# SCH_BlackRacer_team.net
KiCad netlist of a schematic drawn in EasyEDA
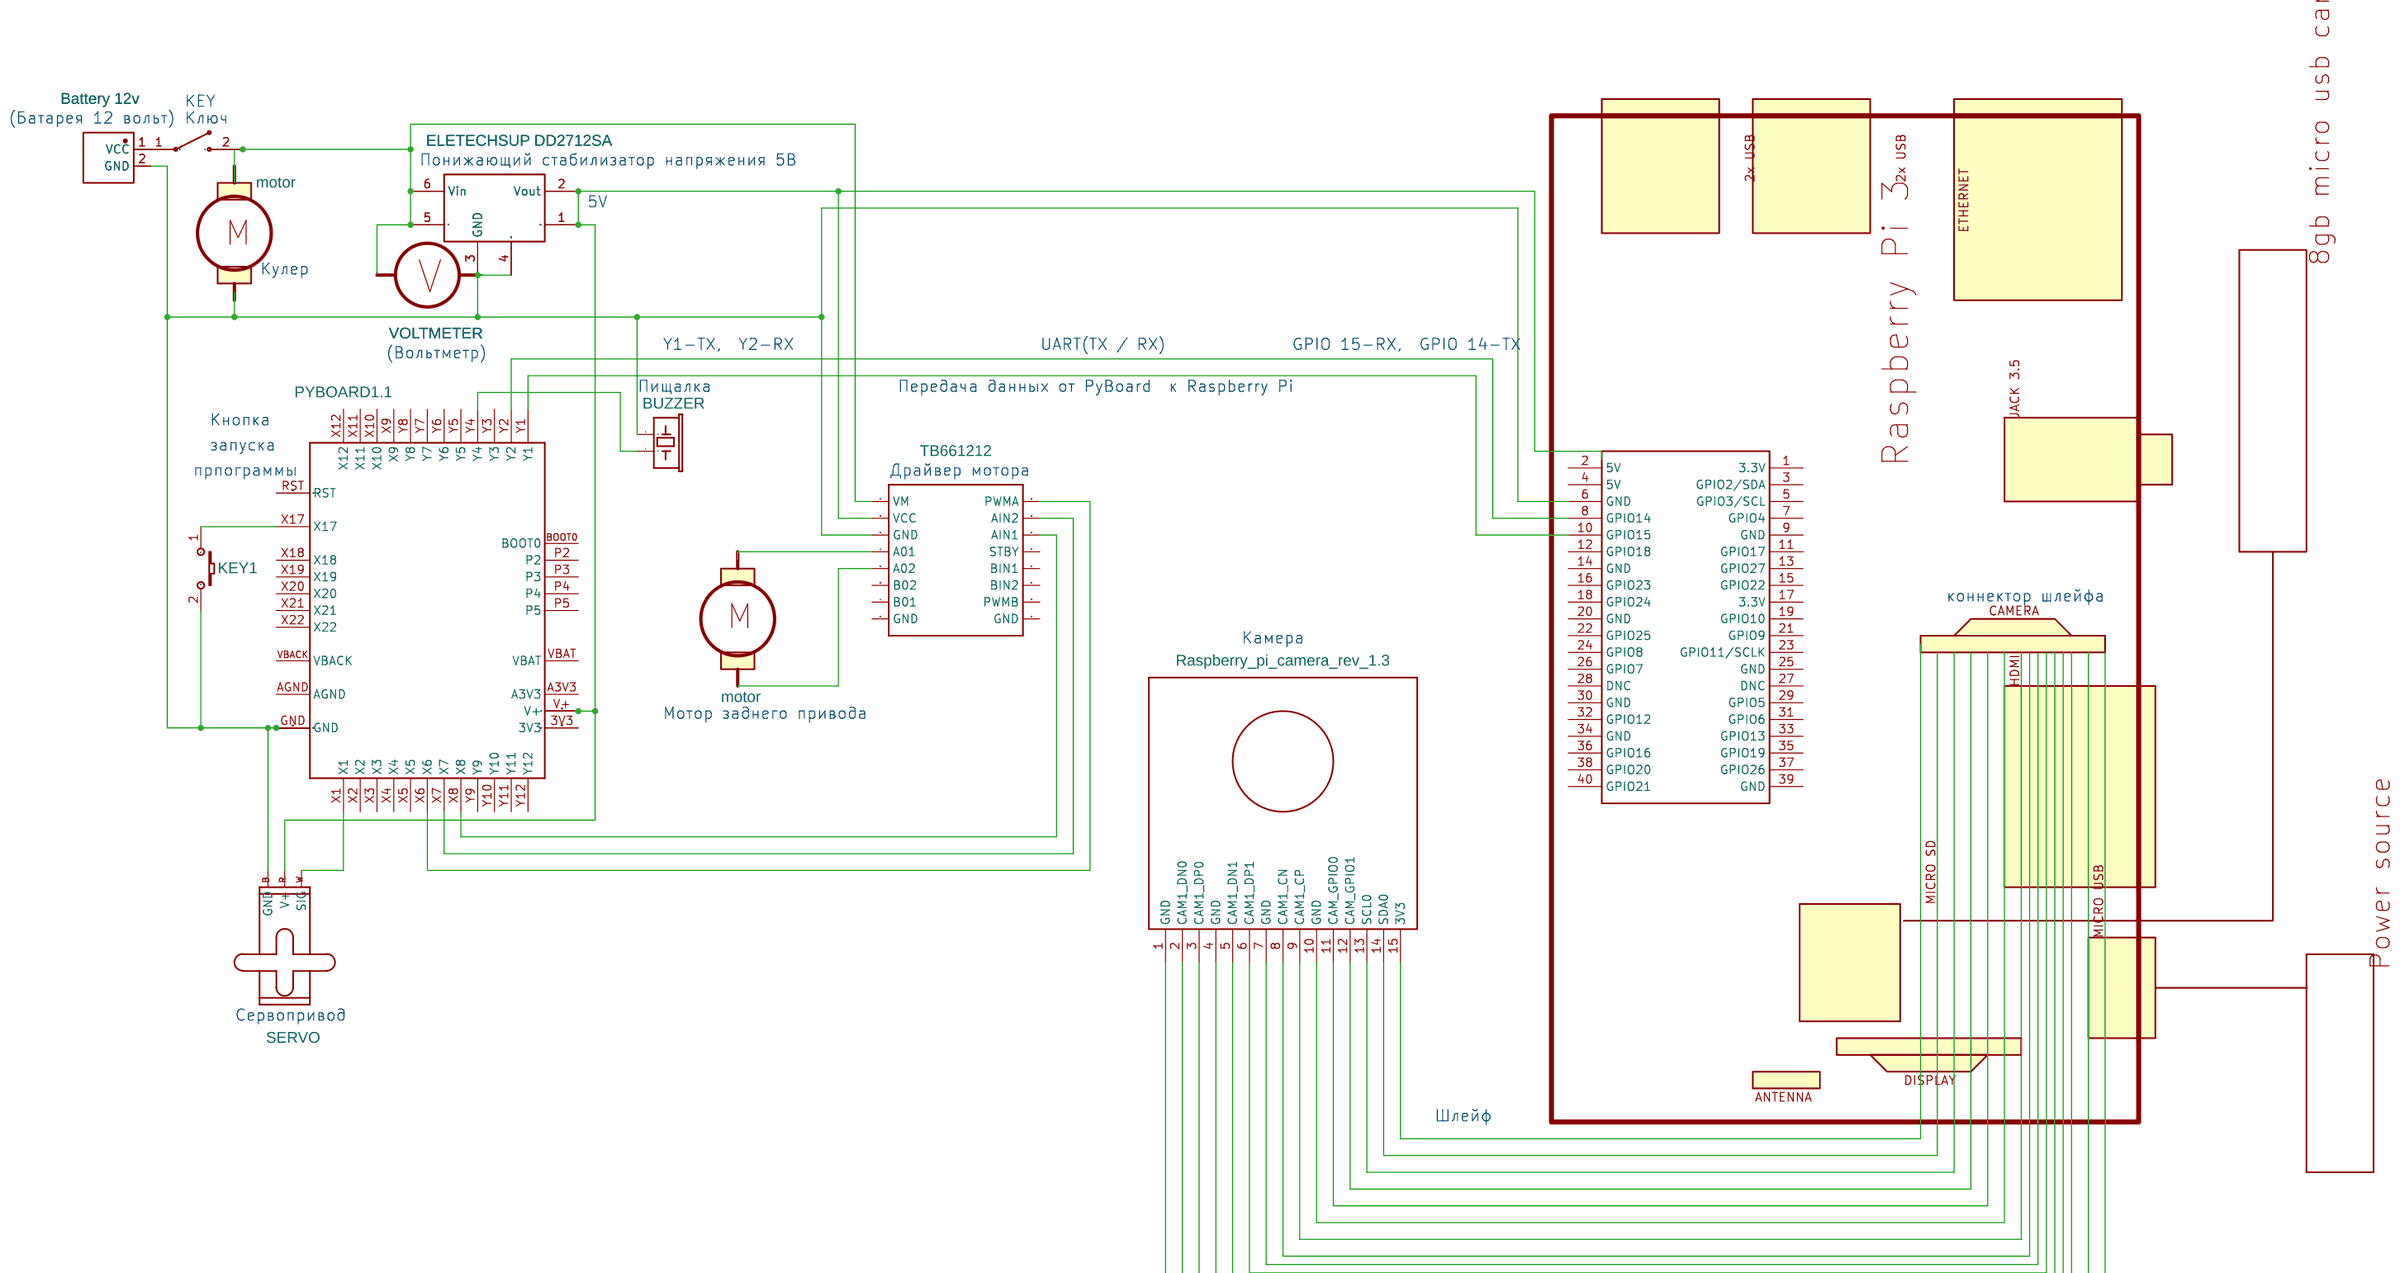
[diagram p0: schematic sheet]

(export (version "E")
  (design (tool "Eeschema 10.0.6"))
  (components
    (comp (ref "1") (value "PYBOARD1.1") (libsource (lib "") (part "PYBOARD1.1")))
    (comp (ref "KEY1")
      (value "K2-3.6×6.1_SMD")
      (fields
        (field (name "BOM_Manufacturer Part") "K2-1107ST-A4SW-06")
        (field (name "BOM_Supplier Part") "C118141")
      )
      (libsource (lib "") (part "K2-3.6×6.1_SMD"))
    )
    (comp (ref "M1") (value "SERVO") (libsource (lib "") (part "SERVO")))
    (comp (ref "M2") (value "motor") (libsource (lib "") (part "motor")))
    (comp (ref "M4") (value "motor") (libsource (lib "") (part "motor_1")))
    (comp (ref "P1") (value "VOLTMETER") (libsource (lib "") (part "VOLTMETER_XL")))
    (comp (ref "SG1") (value "BUZZER") (libsource (lib "") (part "BUZZER")))
    (comp (ref "U1") (value "ELETECHSUP DD2712SA") (libsource (lib "") (part "DD2712SA")))
    (comp (ref "U2")
      (value "Raspberry Pi")
      (fields
        (field (name "BOM_Manufacturer Part") "RASPBERRY PI 3 Model B")
        (field (name "BOM_Supplier Part") "Raspberry Pi 3-B")
      )
      (libsource (lib "") (part "Raspberry Pi"))
    )
    (comp (ref "U4") (value "Battery 12v") (libsource (lib "") (part "Battery")))
    (comp (ref "U5")
      (value "Raspberry_pi_camera_rev_1.3")
      (libsource (lib "") (part "Raspberry_pi_camera_rev_1.3"))
    )
    (comp (ref "U7")
      (value "Botton")
      (fields (field (name "BOM_Manufacturer Part") "2A080") (field (name "BOM_Supplier Part") "12131"))
      (libsource (lib "") (part "Botton"))
    )
    (comp (ref "U9") (value "TB661212") (libsource (lib "") (part "TB661212")))
  )
  (nets
    (net (code "1") (name "Net-(1-3V3-Pad3V3-1)") (class "Default")
      (node (ref "1") (pin "3V3") (pinfunction "3V3_3V3") (pintype "bidirectional"))
      (node (ref "1") (pin "3V3-1") (pinfunction "3V3_3V3-1") (pintype "bidirectional"))
    )
    (net (code "2") (name "Net-(1-PadRST)") (class "Default")
      (node (ref "1") (pin "RST") (pinfunction "RST_RST") (pintype "bidirectional"))
      (node (ref "1") (pin "RST1") (pinfunction "RST_RST1") (pintype "bidirectional"))
    )
    (net (code "3") (name "Net-(1-PadX17)") (class "Default")
      (node (ref "1") (pin "X17") (pinfunction "X17_X17") (pintype "bidirectional"))
      (node (ref "KEY1") (pin "1") (pinfunction "1_1") (pintype "unspecified"))
    )
    (net (code "4") (name "Net-(M1-GND)") (class "Default")
      (node (ref "1") (pin "GND") (pinfunction "GND_GND") (pintype "bidirectional"))
      (node (ref "1") (pin "GND0") (pinfunction "GND_GND0") (pintype "bidirectional"))
      (node (ref "1") (pin "GND1") (pinfunction "GND_GND1") (pintype "bidirectional"))
      (node (ref "1") (pin "GND2") (pinfunction "GND_GND2") (pintype "bidirectional"))
      (node (ref "1") (pin "GND3") (pinfunction "GND_GND3") (pintype "bidirectional"))
      (node (ref "1") (pin "GND4") (pinfunction "GND_GND4") (pintype "bidirectional"))
      (node (ref "1") (pin "GND5") (pinfunction "GND_GND5") (pintype "bidirectional"))
      (node (ref "1") (pin "GND6") (pinfunction "GND_GND6") (pintype "bidirectional"))
      (node (ref "KEY1") (pin "2") (pinfunction "2_2") (pintype "unspecified"))
      (node (ref "M1") (pin "3") (pinfunction "GND_3") (pintype "bidirectional"))
      (node (ref "P1") (pin "2") (pinfunction "B_2") (pintype "unspecified"))
      (node (ref "SG1") (pin "+") (pinfunction "1_+") (pintype "unspecified"))
      (node (ref "U1") (pin "3") (pinfunction "GND_3") (pintype "unspecified"))
      (node (ref "U1") (pin "4") (pinfunction "GND_4") (pintype "unspecified"))
      (node (ref "U2") (pin "6") (pinfunction "GND_6") (pintype "unspecified"))
      (node (ref "U4") (pin "2") (pinfunction "GND_2") (pintype "unspecified"))
      (node (ref "U9") (pin "GND") (pinfunction "GND_GND") (pintype "passive"))
    )
    (net (code "5") (name "Net-(M1-SIG)") (class "Default")
      (node (ref "1") (pin "X1") (pinfunction "X1_X1") (pintype "bidirectional"))
      (node (ref "M1") (pin "1") (pinfunction "SIG_1") (pintype "bidirectional"))
    )
    (net (code "6") (name "Net-(M1-V+)") (class "Default")
      (node (ref "1") (pin "V+") (pinfunction "V+_V+") (pintype "bidirectional"))
      (node (ref "1") (pin "V+1") (pinfunction "V+_V+1") (pintype "bidirectional"))
      (node (ref "1") (pin "V+2") (pinfunction "V+_V+2") (pintype "bidirectional"))
      (node (ref "1") (pin "V+3") (pinfunction "V+_V+3") (pintype "bidirectional"))
      (node (ref "1") (pin "V+4") (pinfunction "V+_V+4") (pintype "bidirectional"))
      (node (ref "1") (pin "V+5") (pinfunction "V+_V+5") (pintype "bidirectional"))
      (node (ref "1") (pin "V+6") (pinfunction "V+_V+6") (pintype "bidirectional"))
      (node (ref "M1") (pin "2") (pinfunction "V+_2") (pintype "bidirectional"))
      (node (ref "U1") (pin "1") (pinfunction "Vout_1") (pintype "unspecified"))
      (node (ref "U1") (pin "2") (pinfunction "Vout_2") (pintype "unspecified"))
      (node (ref "U9") (pin "VCC") (pinfunction "VCC_VCC") (pintype "passive"))
    )
    (net (code "7") (name "Net-(P1-A)") (class "Default")
      (node (ref "M2") (pin "2") (pinfunction "2_2") (pintype "unspecified"))
      (node (ref "P1") (pin "1") (pinfunction "A_1") (pintype "unspecified"))
      (node (ref "U1") (pin "5") (pinfunction "Vin_5") (pintype "unspecified"))
      (node (ref "U1") (pin "6") (pinfunction "Vin_6") (pintype "unspecified"))
      (node (ref "U7") (pin "2") (pinfunction "1_2") (pintype "unspecified"))
      (node (ref "U9") (pin "VM") (pinfunction "VM_VM") (pintype "passive"))
    )
    (net (code "8") (name "Net-(SG1-2)") (class "Default")
      (node (ref "1") (pin "Y4") (pinfunction "Y4_Y4") (pintype "bidirectional"))
      (node (ref "SG1") (pin "-") (pinfunction "2_-") (pintype "unspecified"))
    )
    (net (code "9") (name "Net-(U2-GPIO14)") (class "Default")
      (node (ref "1") (pin "Y2") (pinfunction "Y2_Y2") (pintype "bidirectional"))
      (node (ref "U2") (pin "8") (pinfunction "GPIO14_8") (pintype "bidirectional"))
    )
    (net (code "10") (name "Net-(U2-GPIO15)") (class "Default")
      (node (ref "1") (pin "Y1") (pinfunction "Y1_Y1") (pintype "bidirectional"))
      (node (ref "U2") (pin "10") (pinfunction "GPIO15_10") (pintype "bidirectional"))
    )
    (net (code "11") (name "Net-(U9-AIN1)") (class "Default")
      (node (ref "1") (pin "X8") (pinfunction "X8_X8") (pintype "bidirectional"))
      (node (ref "U9") (pin "14") (pinfunction "AIN1_14") (pintype "unspecified"))
    )
    (net (code "12") (name "Net-(U9-AIN2)") (class "Default")
      (node (ref "1") (pin "X7") (pinfunction "X7_X7") (pintype "bidirectional"))
      (node (ref "U9") (pin "15") (pinfunction "AIN2_15") (pintype "unspecified"))
    )
    (net (code "13") (name "Net-(U9-PWMA)") (class "Default")
      (node (ref "1") (pin "X6") (pinfunction "X6_X6") (pintype "bidirectional"))
      (node (ref "U9") (pin "16") (pinfunction "PWMA_16") (pintype "unspecified"))
    )
    (net (code "14") (name "unconnected-(1-PadA3V3)") (class "Default")
      (node (ref "1") (pin "A3V3") (pinfunction "A3V3_A3V3") (pintype "bidirectional"))
    )
    (net (code "15") (name "unconnected-(1-PadAGND)") (class "Default")
      (node (ref "1") (pin "AGND") (pinfunction "AGND_AGND") (pintype "bidirectional"))
    )
    (net (code "16") (name "unconnected-(1-PadBOOT0)") (class "Default")
      (node (ref "1") (pin "BOOT0") (pinfunction "BOOT0_BOOT0") (pintype "bidirectional"))
    )
    (net (code "17") (name "unconnected-(1-PadP2)") (class "Default")
      (node (ref "1") (pin "P2") (pinfunction "P2_P2") (pintype "bidirectional"))
    )
    (net (code "18") (name "unconnected-(1-PadP3)") (class "Default")
      (node (ref "1") (pin "P3") (pinfunction "P3_P3") (pintype "bidirectional"))
    )
    (net (code "19") (name "unconnected-(1-PadP4)") (class "Default")
      (node (ref "1") (pin "P4") (pinfunction "P4_P4") (pintype "bidirectional"))
    )
    (net (code "20") (name "unconnected-(1-PadP5)") (class "Default")
      (node (ref "1") (pin "P5") (pinfunction "P5_P5") (pintype "bidirectional"))
    )
    (net (code "21") (name "unconnected-(1-PadVBACK)") (class "Default")
      (node (ref "1") (pin "VBACK") (pinfunction "VBACK_VBACK") (pintype "bidirectional"))
    )
    (net (code "22") (name "unconnected-(1-PadVBAT)") (class "Default")
      (node (ref "1") (pin "VBAT") (pinfunction "VBAT_VBAT") (pintype "bidirectional"))
    )
    (net (code "23") (name "unconnected-(1-PadX2)") (class "Default")
      (node (ref "1") (pin "X2") (pinfunction "X2_X2") (pintype "bidirectional"))
    )
    (net (code "24") (name "unconnected-(1-PadX3)") (class "Default")
      (node (ref "1") (pin "X3") (pinfunction "X3_X3") (pintype "bidirectional"))
    )
    (net (code "25") (name "unconnected-(1-PadX4)") (class "Default")
      (node (ref "1") (pin "X4") (pinfunction "X4_X4") (pintype "bidirectional"))
    )
    (net (code "26") (name "unconnected-(1-PadX5)") (class "Default")
      (node (ref "1") (pin "X5") (pinfunction "X5_X5") (pintype "bidirectional"))
    )
    (net (code "27") (name "unconnected-(1-PadX9)") (class "Default")
      (node (ref "1") (pin "X9") (pinfunction "X9_X9") (pintype "bidirectional"))
    )
    (net (code "28") (name "unconnected-(1-PadX10)") (class "Default")
      (node (ref "1") (pin "X10") (pinfunction "X10_X10") (pintype "bidirectional"))
    )
    (net (code "29") (name "unconnected-(1-PadX11)") (class "Default")
      (node (ref "1") (pin "X11") (pinfunction "X11_X11") (pintype "bidirectional"))
    )
    (net (code "30") (name "unconnected-(1-PadX12)") (class "Default")
      (node (ref "1") (pin "X12") (pinfunction "X12_X12") (pintype "bidirectional"))
    )
    (net (code "31") (name "unconnected-(1-PadX18)") (class "Default")
      (node (ref "1") (pin "X18") (pinfunction "X18_X18") (pintype "bidirectional"))
    )
    (net (code "32") (name "unconnected-(1-PadX19)") (class "Default")
      (node (ref "1") (pin "X19") (pinfunction "X19_X19") (pintype "bidirectional"))
    )
    (net (code "33") (name "unconnected-(1-PadX20)") (class "Default")
      (node (ref "1") (pin "X20") (pinfunction "X20_X20") (pintype "bidirectional"))
    )
    (net (code "34") (name "unconnected-(1-PadX21)") (class "Default")
      (node (ref "1") (pin "X21") (pinfunction "X21_X21") (pintype "bidirectional"))
    )
    (net (code "35") (name "unconnected-(1-PadX22)") (class "Default")
      (node (ref "1") (pin "X22") (pinfunction "X22_X22") (pintype "bidirectional"))
    )
    (net (code "36") (name "unconnected-(1-PadY3)") (class "Default")
      (node (ref "1") (pin "Y3") (pinfunction "Y3_Y3") (pintype "bidirectional"))
    )
    (net (code "37") (name "unconnected-(1-PadY5)") (class "Default")
      (node (ref "1") (pin "Y5") (pinfunction "Y5_Y5") (pintype "bidirectional"))
    )
    (net (code "38") (name "unconnected-(1-PadY6)") (class "Default")
      (node (ref "1") (pin "Y6") (pinfunction "Y6_Y6") (pintype "bidirectional"))
    )
    (net (code "39") (name "unconnected-(1-PadY7)") (class "Default")
      (node (ref "1") (pin "Y7") (pinfunction "Y7_Y7") (pintype "bidirectional"))
    )
    (net (code "40") (name "unconnected-(1-PadY8)") (class "Default")
      (node (ref "1") (pin "Y8") (pinfunction "Y8_Y8") (pintype "bidirectional"))
    )
    (net (code "41") (name "unconnected-(1-PadY9)") (class "Default")
      (node (ref "1") (pin "Y9") (pinfunction "Y9_Y9") (pintype "bidirectional"))
    )
    (net (code "42") (name "unconnected-(1-PadY10)") (class "Default")
      (node (ref "1") (pin "Y10") (pinfunction "Y10_Y10") (pintype "bidirectional"))
    )
    (net (code "43") (name "unconnected-(1-PadY11)") (class "Default")
      (node (ref "1") (pin "Y11") (pinfunction "Y11_Y11") (pintype "bidirectional"))
    )
    (net (code "44") (name "unconnected-(1-PadY12)") (class "Default")
      (node (ref "1") (pin "Y12") (pinfunction "Y12_Y12") (pintype "bidirectional"))
    )
    (net (code "45") (name "unconnected-(M4-Pad2)") (class "Default")
      (node (ref "M4") (pin "2") (pinfunction "2_2") (pintype "unspecified"))
    )
    (net (code "46") (name "unconnected-(U2-3.3V-Pad1)") (class "Default")
      (node (ref "U2") (pin "1") (pinfunction "3.3V_1") (pintype "passive"))
    )
    (net (code "47") (name "unconnected-(U2-3.3V-Pad17)") (class "Default")
      (node (ref "U2") (pin "17") (pinfunction "3.3V_17") (pintype "passive"))
    )
    (net (code "48") (name "unconnected-(U2-5V-Pad2)") (class "Default")
      (node (ref "U2") (pin "2") (pinfunction "5V_2") (pintype "passive"))
    )
    (net (code "49") (name "unconnected-(U2-5V-Pad4)") (class "Default")
      (node (ref "U2") (pin "4") (pinfunction "5V_4") (pintype "passive"))
    )
    (net (code "50") (name "unconnected-(U2-DNC-Pad27)") (class "Default")
      (node (ref "U2") (pin "27") (pinfunction "DNC_27") (pintype "unspecified"))
    )
    (net (code "51") (name "unconnected-(U2-DNC-Pad28)") (class "Default")
      (node (ref "U2") (pin "28") (pinfunction "DNC_28") (pintype "unspecified"))
    )
    (net (code "52") (name "unconnected-(U2-GND-Pad9)") (class "Default")
      (node (ref "U2") (pin "9") (pinfunction "GND_9") (pintype "unspecified"))
    )
    (net (code "53") (name "unconnected-(U2-GND-Pad14)") (class "Default")
      (node (ref "U2") (pin "14") (pinfunction "GND_14") (pintype "unspecified"))
    )
    (net (code "54") (name "unconnected-(U2-GND-Pad20)") (class "Default")
      (node (ref "U2") (pin "20") (pinfunction "GND_20") (pintype "unspecified"))
    )
    (net (code "55") (name "unconnected-(U2-GND-Pad25)") (class "Default")
      (node (ref "U2") (pin "25") (pinfunction "GND_25") (pintype "unspecified"))
    )
    (net (code "56") (name "unconnected-(U2-GND-Pad30)") (class "Default")
      (node (ref "U2") (pin "30") (pinfunction "GND_30") (pintype "unspecified"))
    )
    (net (code "57") (name "unconnected-(U2-GND-Pad34)") (class "Default")
      (node (ref "U2") (pin "34") (pinfunction "GND_34") (pintype "unspecified"))
    )
    (net (code "58") (name "unconnected-(U2-GND-Pad39)") (class "Default")
      (node (ref "U2") (pin "39") (pinfunction "GND_39") (pintype "unspecified"))
    )
    (net (code "59") (name "unconnected-(U2-GPIO2{slash}SDA-Pad3)") (class "Default")
      (node (ref "U2") (pin "3") (pinfunction "GPIO2/SDA_3") (pintype "bidirectional"))
    )
    (net (code "60") (name "unconnected-(U2-GPIO3{slash}SCL-Pad5)") (class "Default")
      (node (ref "U2") (pin "5") (pinfunction "GPIO3/SCL_5") (pintype "bidirectional"))
    )
    (net (code "61") (name "unconnected-(U2-GPIO4-Pad7)") (class "Default")
      (node (ref "U2") (pin "7") (pinfunction "GPIO4_7") (pintype "bidirectional"))
    )
    (net (code "62") (name "unconnected-(U2-GPIO5-Pad29)") (class "Default")
      (node (ref "U2") (pin "29") (pinfunction "GPIO5_29") (pintype "bidirectional"))
    )
    (net (code "63") (name "unconnected-(U2-GPIO6-Pad31)") (class "Default")
      (node (ref "U2") (pin "31") (pinfunction "GPIO6_31") (pintype "bidirectional"))
    )
    (net (code "64") (name "unconnected-(U2-GPIO7-Pad26)") (class "Default")
      (node (ref "U2") (pin "26") (pinfunction "GPIO7_26") (pintype "bidirectional"))
    )
    (net (code "65") (name "unconnected-(U2-GPIO8-Pad24)") (class "Default")
      (node (ref "U2") (pin "24") (pinfunction "GPIO8_24") (pintype "bidirectional"))
    )
    (net (code "66") (name "unconnected-(U2-GPIO9-Pad21)") (class "Default")
      (node (ref "U2") (pin "21") (pinfunction "GPIO9_21") (pintype "bidirectional"))
    )
    (net (code "67") (name "unconnected-(U2-GPIO10-Pad19)") (class "Default")
      (node (ref "U2") (pin "19") (pinfunction "GPIO10_19") (pintype "bidirectional"))
    )
    (net (code "68") (name "unconnected-(U2-GPIO11{slash}SCLK-Pad23)") (class "Default")
      (node (ref "U2") (pin "23") (pinfunction "GPIO11/SCLK_23") (pintype "bidirectional"))
    )
    (net (code "69") (name "unconnected-(U2-GPIO12-Pad32)") (class "Default")
      (node (ref "U2") (pin "32") (pinfunction "GPIO12_32") (pintype "bidirectional"))
    )
    (net (code "70") (name "unconnected-(U2-GPIO13-Pad33)") (class "Default")
      (node (ref "U2") (pin "33") (pinfunction "GPIO13_33") (pintype "bidirectional"))
    )
    (net (code "71") (name "unconnected-(U2-GPIO16-Pad36)") (class "Default")
      (node (ref "U2") (pin "36") (pinfunction "GPIO16_36") (pintype "bidirectional"))
    )
    (net (code "72") (name "unconnected-(U2-GPIO17-Pad11)") (class "Default")
      (node (ref "U2") (pin "11") (pinfunction "GPIO17_11") (pintype "bidirectional"))
    )
    (net (code "73") (name "unconnected-(U2-GPIO18-Pad12)") (class "Default")
      (node (ref "U2") (pin "12") (pinfunction "GPIO18_12") (pintype "bidirectional"))
    )
    (net (code "74") (name "unconnected-(U2-GPIO19-Pad35)") (class "Default")
      (node (ref "U2") (pin "35") (pinfunction "GPIO19_35") (pintype "bidirectional"))
    )
    (net (code "75") (name "unconnected-(U2-GPIO20-Pad38)") (class "Default")
      (node (ref "U2") (pin "38") (pinfunction "GPIO20_38") (pintype "bidirectional"))
    )
    (net (code "76") (name "unconnected-(U2-GPIO21-Pad40)") (class "Default")
      (node (ref "U2") (pin "40") (pinfunction "GPIO21_40") (pintype "bidirectional"))
    )
    (net (code "77") (name "unconnected-(U2-GPIO22-Pad15)") (class "Default")
      (node (ref "U2") (pin "15") (pinfunction "GPIO22_15") (pintype "bidirectional"))
    )
    (net (code "78") (name "unconnected-(U2-GPIO23-Pad16)") (class "Default")
      (node (ref "U2") (pin "16") (pinfunction "GPIO23_16") (pintype "bidirectional"))
    )
    (net (code "79") (name "unconnected-(U2-GPIO24-Pad18)") (class "Default")
      (node (ref "U2") (pin "18") (pinfunction "GPIO24_18") (pintype "bidirectional"))
    )
    (net (code "80") (name "unconnected-(U2-GPIO25-Pad22)") (class "Default")
      (node (ref "U2") (pin "22") (pinfunction "GPIO25_22") (pintype "bidirectional"))
    )
    (net (code "81") (name "unconnected-(U2-GPIO26-Pad37)") (class "Default")
      (node (ref "U2") (pin "37") (pinfunction "GPIO26_37") (pintype "bidirectional"))
    )
    (net (code "82") (name "unconnected-(U2-GPIO27-Pad13)") (class "Default")
      (node (ref "U2") (pin "13") (pinfunction "GPIO27_13") (pintype "bidirectional"))
    )
    (net (code "83") (name "unconnected-(U4-VCC-Pad1)") (class "Default")
      (node (ref "U4") (pin "1") (pinfunction "VCC_1") (pintype "unspecified"))
    )
    (net (code "84") (name "unconnected-(U5-3V3-Pad15)") (class "Default")
      (node (ref "U5") (pin "15") (pinfunction "3V3_15") (pintype "unspecified"))
    )
    (net (code "85") (name "unconnected-(U5-CAM1_CN-Pad8)") (class "Default")
      (node (ref "U5") (pin "8") (pinfunction "CAM1_CN_8") (pintype "unspecified"))
    )
    (net (code "86") (name "unconnected-(U5-CAM1_CP-Pad9)") (class "Default")
      (node (ref "U5") (pin "9") (pinfunction "CAM1_CP_9") (pintype "unspecified"))
    )
    (net (code "87") (name "unconnected-(U5-CAM1_DN0-Pad2)") (class "Default")
      (node (ref "U5") (pin "2") (pinfunction "CAM1_DN0_2") (pintype "unspecified"))
    )
    (net (code "88") (name "unconnected-(U5-CAM1_DN1-Pad5)") (class "Default")
      (node (ref "U5") (pin "5") (pinfunction "CAM1_DN1_5") (pintype "unspecified"))
    )
    (net (code "89") (name "unconnected-(U5-CAM1_DP0-Pad3)") (class "Default")
      (node (ref "U5") (pin "3") (pinfunction "CAM1_DP0_3") (pintype "unspecified"))
    )
    (net (code "90") (name "unconnected-(U5-CAM1_DP1-Pad6)") (class "Default")
      (node (ref "U5") (pin "6") (pinfunction "CAM1_DP1_6") (pintype "unspecified"))
    )
    (net (code "91") (name "unconnected-(U5-CAM_GPIO0-Pad11)") (class "Default")
      (node (ref "U5") (pin "11") (pinfunction "CAM_GPIO0_11") (pintype "unspecified"))
    )
    (net (code "92") (name "unconnected-(U5-CAM_GPIO1-Pad12)") (class "Default")
      (node (ref "U5") (pin "12") (pinfunction "CAM_GPIO1_12") (pintype "unspecified"))
    )
    (net (code "93") (name "unconnected-(U5-GND-Pad1)") (class "Default")
      (node (ref "U5") (pin "1") (pinfunction "GND_1") (pintype "unspecified"))
    )
    (net (code "94") (name "unconnected-(U5-GND-Pad4)") (class "Default")
      (node (ref "U5") (pin "4") (pinfunction "GND_4") (pintype "unspecified"))
    )
    (net (code "95") (name "unconnected-(U5-GND-Pad7)") (class "Default")
      (node (ref "U5") (pin "7") (pinfunction "GND_7") (pintype "unspecified"))
    )
    (net (code "96") (name "unconnected-(U5-GND-Pad10)") (class "Default")
      (node (ref "U5") (pin "10") (pinfunction "GND_10") (pintype "unspecified"))
    )
    (net (code "97") (name "unconnected-(U5-SCL0-Pad13)") (class "Default")
      (node (ref "U5") (pin "13") (pinfunction "SCL0_13") (pintype "unspecified"))
    )
    (net (code "98") (name "unconnected-(U5-SDA0-Pad14)") (class "Default")
      (node (ref "U5") (pin "14") (pinfunction "SDA0_14") (pintype "unspecified"))
    )
    (net (code "99") (name "unconnected-(U7-2-Pad1)") (class "Default")
      (node (ref "U7") (pin "1") (pinfunction "2_1") (pintype "unspecified"))
    )
    (net (code "100") (name "unconnected-(U9-A01-Pad4)") (class "Default")
      (node (ref "U9") (pin "4") (pinfunction "A01_4") (pintype "unspecified"))
    )
    (net (code "101") (name "unconnected-(U9-A02-Pad5)") (class "Default")
      (node (ref "U9") (pin "5") (pinfunction "A02_5") (pintype "unspecified"))
    )
    (net (code "102") (name "unconnected-(U9-B01-Pad7)") (class "Default")
      (node (ref "U9") (pin "7") (pinfunction "B01_7") (pintype "unspecified"))
    )
    (net (code "103") (name "unconnected-(U9-B02-Pad6)") (class "Default")
      (node (ref "U9") (pin "6") (pinfunction "B02_6") (pintype "unspecified"))
    )
    (net (code "104") (name "unconnected-(U9-BIN1-Pad12)") (class "Default")
      (node (ref "U9") (pin "12") (pinfunction "BIN1_12") (pintype "unspecified"))
    )
    (net (code "105") (name "unconnected-(U9-BIN2-Pad11)") (class "Default")
      (node (ref "U9") (pin "11") (pinfunction "BIN2_11") (pintype "unspecified"))
    )
    (net (code "106") (name "unconnected-(U9-GND-Pad8)") (class "Default")
      (node (ref "U9") (pin "8") (pinfunction "GND_8") (pintype "passive"))
    )
    (net (code "107") (name "unconnected-(U9-GND-Pad56)") (class "Default")
      (node (ref "U9") (pin "56") (pinfunction "GND_56") (pintype "passive"))
    )
    (net (code "108") (name "unconnected-(U9-PWMB-Pad10)") (class "Default")
      (node (ref "U9") (pin "10") (pinfunction "PWMB_10") (pintype "unspecified"))
    )
    (net (code "109") (name "unconnected-(U9-STBY-Pad13)") (class "Default")
      (node (ref "U9") (pin "13") (pinfunction "STBY_13") (pintype "unspecified"))
    )
  )
)
